# Processor.net
KiCad netlist of a schematic drawn in Altium Designer
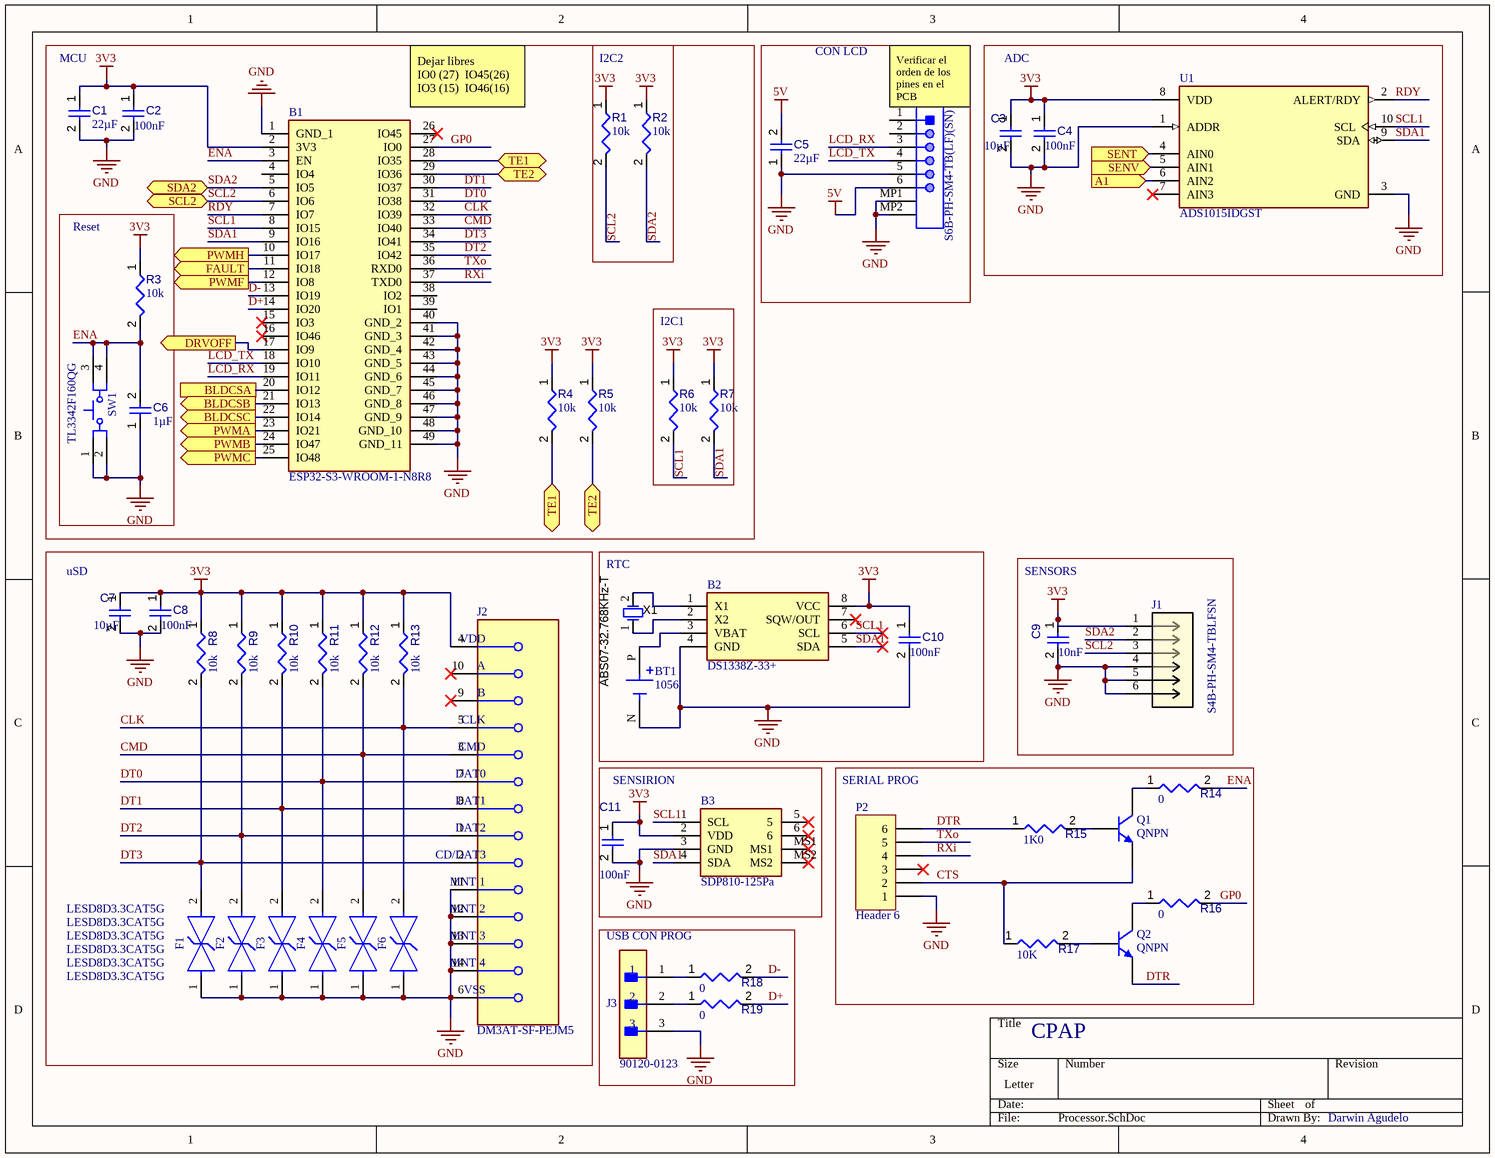
[diagram p0: Processor.SchDoc]

(export (version "E")
  (design (tool "Eeschema 10.0.6"))
  (components
    (comp (ref "B1")
      (value "ESP32-S3-WROOM-1-N8R8")
      (footprint "ESP32S3WROOM1N8R8")
      (fields (field (name "MOUSER PART NUMBER") "356-EP32S3WROOM1N8R8"))
      (libsource (lib "ESP32-S3-WROOM-1-N8R8") (part "ESP32-S3-WROOM-1-N8R8"))
    )
    (comp (ref "B2")
      (value "DS1338Z-33+")
      (footprint "SOIC127P600X175-8N")
      (fields (field (name "MOUSER PART NUMBER") "700-DS1338Z-33"))
      (libsource (lib "DS1338Z-33+") (part "DS1338Z-33+"))
    )
    (comp (ref "B3")
      (value "SDP810-125Pa")
      (footprint "SDP810125Pa")
      (description "Sensirion SDP810-125PA, Differential Pressure Sensor +125Pa 4-Pin")
      (fields
        (field (name "MOUSER PART NUMBER") "403-SDP810-125PA")
        (field (name "ARROW PART NUMBER") "SDP810-125PA")
      )
      (libsource (lib "SDP810-125Pa") (part "SDP810-125Pa"))
    )
    (comp (ref "BT1") (value "1056") (footprint "BAT_1056") (libsource (lib "1056") (part "1056")))
    (comp (ref "C1")
      (value "22µF")
      (footprint "CAPC0805(2012)145_L")
      (description "Chip Capacitor, 22µF +/-40%, 16V, 0805, Thickness 1.45 mm")
      (fields (field (name "TOLERANCE") "5%") (field (name "Comment") "Capacitor 22µF +/-40% 16V 0805"))
      (libsource (lib "UdeA") (part "CAP-NP-2"))
    )
    (comp (ref "C2")
      (value "100nF")
      (footprint "CAPC1608X90X40NL10T20")
      (description "Chip Capacitor, 100 nF, +/- 10%, 50 V, 0603 (1608 Metric)")
      (fields (field (name "TOLERANCE") "10%") (field (name "Comment") "Capacitor 100 nF +/-10% 50 V 0603"))
      (libsource (lib "UdeA") (part "CAP-NP-2"))
    )
    (comp (ref "C3")
      (value "10µF")
      (footprint "CAPC0805(2012)145_L")
      (description "Chip Capacitor, 22µF +/-40%, 16V, 0805, Thickness 1.45 mm")
      (fields (field (name "TOLERANCE") "5%") (field (name "Comment") "Capacitor 22µF +/-40% 16V 0805"))
      (libsource (lib "UdeA") (part "CAP-NP-2"))
    )
    (comp (ref "C4")
      (value "100nF")
      (footprint "CAPC1608X90X40NL10T20")
      (description "Chip Capacitor, 100 nF, +/- 10%, 50 V, 0603 (1608 Metric)")
      (fields (field (name "TOLERANCE") "10%") (field (name "Comment") "Capacitor 100 nF +/-10% 50 V 0603"))
      (libsource (lib "UdeA") (part "CAP-NP-2"))
    )
    (comp (ref "C5")
      (value "22µF")
      (footprint "CAPC0805(2012)145_L")
      (description "Chip Capacitor, 22µF +/-40%, 16V, 0805, Thickness 1.45 mm")
      (fields (field (name "TOLERANCE") "5%") (field (name "Comment") "Capacitor 22µF +/-40% 16V 0805"))
      (libsource (lib "UdeA") (part "CAP-NP-2"))
    )
    (comp (ref "C6")
      (value "1µF")
      (footprint "CAPC0603(1608)100_L")
      (description "Chip Capacitor, 1µF +/-40%, 50V, 0603, Thickness 1 mm")
      (fields (field (name "TOLERANCE") "10%") (field (name "Comment") "Capacitor 1µF +/-40% 50V 0603"))
      (libsource (lib "UdeA") (part "CAP-NP-2"))
    )
    (comp (ref "C7")
      (value "10µF")
      (footprint "CAPC0805(2012)145_L")
      (description "Chip Capacitor, 22µF +/-40%, 16V, 0805, Thickness 1.45 mm")
      (fields (field (name "TOLERANCE") "5%") (field (name "Comment") "Capacitor 22µF +/-40% 16V 0805"))
      (libsource (lib "UdeA") (part "CAP-NP-2"))
    )
    (comp (ref "C8")
      (value "100nF")
      (footprint "CAPC1608X90X40NL10T20")
      (description "Chip Capacitor, 100 nF, +/- 10%, 50 V, 0603 (1608 Metric)")
      (fields (field (name "TOLERANCE") "10%") (field (name "Comment") "Capacitor 100 nF +/-10% 50 V 0603"))
      (libsource (lib "UdeA") (part "CAP-NP-2"))
    )
    (comp (ref "C9")
      (value "10nF")
      (footprint "CAPC1608X90X40NL10T20")
      (description "Chip Capacitor, 100 nF, +/- 10%, 50 V, 0603 (1608 Metric)")
      (fields (field (name "TOLERANCE") "10%") (field (name "Comment") "Capacitor 100 nF +/-10% 50 V 0603"))
      (libsource (lib "UdeA") (part "CAP-NP-2"))
    )
    (comp (ref "C10")
      (value "100nF")
      (footprint "CAPC1608X90X40NL10T20")
      (description "Chip Capacitor, 100 nF, +/- 10%, 50 V, 0603 (1608 Metric)")
      (fields (field (name "TOLERANCE") "10%") (field (name "Comment") "Capacitor 100 nF +/-10% 50 V 0603"))
      (libsource (lib "UdeA") (part "CAP-NP-2"))
    )
    (comp (ref "C11")
      (value "100nF")
      (footprint "CAPC1608X90X40NL10T20")
      (description "Chip Capacitor, 100 nF, +/- 10%, 50 V, 0603 (1608 Metric)")
      (fields (field (name "TOLERANCE") "10%") (field (name "Comment") "Capacitor 100 nF +/-10% 50 V 0603"))
      (libsource (lib "UdeA") (part "CAP-NP-2"))
    )
    (comp (ref "F1")
      (value "LESD8D3.3CAT5G")
      (footprint "FP-ESDALC5-1BM2-MFG")
      (description "ESDALC5-1BM2 ESD Suppressors / TVS Diodes Single Line Transil Vbr 5V min 26pF 0")
      (libsource (lib "Altium Content Vault") (part "a9b0225688e8abec59830331bad87f8"))
    )
    (comp (ref "F2")
      (value "LESD8D3.3CAT5G")
      (footprint "FP-ESDALC5-1BM2-MFG")
      (description "ESDALC5-1BM2 ESD Suppressors / TVS Diodes Single Line Transil Vbr 5V min 26pF 0")
      (libsource (lib "Altium Content Vault") (part "a9b0225688e8abec59830331bad87f8"))
    )
    (comp (ref "F3")
      (value "LESD8D3.3CAT5G")
      (footprint "FP-ESDALC5-1BM2-MFG")
      (description "ESDALC5-1BM2 ESD Suppressors / TVS Diodes Single Line Transil Vbr 5V min 26pF 0")
      (libsource (lib "Altium Content Vault") (part "a9b0225688e8abec59830331bad87f8"))
    )
    (comp (ref "F4")
      (value "LESD8D3.3CAT5G")
      (footprint "FP-ESDALC5-1BM2-MFG")
      (description "ESDALC5-1BM2 ESD Suppressors / TVS Diodes Single Line Transil Vbr 5V min 26pF 0")
      (libsource (lib "Altium Content Vault") (part "a9b0225688e8abec59830331bad87f8"))
    )
    (comp (ref "F5")
      (value "LESD8D3.3CAT5G")
      (footprint "FP-ESDALC5-1BM2-MFG")
      (description "ESDALC5-1BM2 ESD Suppressors / TVS Diodes Single Line Transil Vbr 5V min 26pF 0")
      (libsource (lib "Altium Content Vault") (part "a9b0225688e8abec59830331bad87f8"))
    )
    (comp (ref "F6")
      (value "LESD8D3.3CAT5G")
      (footprint "FP-ESDALC5-1BM2-MFG")
      (description "ESDALC5-1BM2 ESD Suppressors / TVS Diodes Single Line Transil Vbr 5V min 26pF 0")
      (libsource (lib "Altium Content Vault") (part "a9b0225688e8abec59830331bad87f8"))
    )
    (comp (ref "J1")
      (value "S4B-PH-SM4-TBLFSN")
      (footprint "CONN_S4B-PH-SM4-TBLFSN_JST")
      (description "No Description Available")
      (libsource (lib "S4B-PH-SM4-TBLFSN") (part "S4B-PH-SM4-TBLFSN"))
    )
    (comp (ref "J2")
      (value "DM3AT-SF-PEJM5")
      (footprint "FP-DM3AT-SF-PEJM5-MFG")
      (description "CONN MICRO SD CARD PUSH-PUSH R/A")
      (libsource (lib "Altium Content Vault") (part "a4e64ec0820c4377148bc1329e4c440"))
    )
    (comp (ref "J3")
      (value "90120-0123")
      (footprint "FP-90120-0123-MFG")
      (description "CONN HEADER VERT 3POS 2.54MM")
      (libsource (lib "Altium Content Vault") (part "0d3f023dd272f625e17a2be33dea85f"))
    )
    (comp (ref "P1")
      (value "S6B-PH-SM4-TB(LF)(SN)")
      (footprint "JST-S6B-PH-SM4-TB(LF)(SN)_V")
      (description "Male Header, Pitch 2 mm, 1 x 6 Position, Height 5.5 mm, -25 to 85 degC")
      (fields (field (name "MANUFACTURER") "JST"))
      (libsource (lib "Altium Content Vault") (part "CN-1P-2M-R6"))
    )
    (comp (ref "P2")
      (value "Header 6")
      (footprint "HDR1X6")
      (description "Header, 6-Pin")
      (fields (field (name "PUBLISHER") "Altium Limited"))
      (libsource (lib "Miscellaneous Connectors") (part "Header 6"))
    )
    (comp (ref "Q1")
      (value "QNPN")
      (footprint "SOT-23B_L")
      (description "NPN Bipolar Transistor")
      (fields (field (name "PUBLISHER") "Altium Limited"))
      (libsource (lib "Miscellaneous Devices") (part "QNPN"))
    )
    (comp (ref "Q2")
      (value "QNPN")
      (footprint "SOT-23B_L")
      (description "NPN Bipolar Transistor")
      (fields (field (name "PUBLISHER") "Altium Limited"))
      (libsource (lib "Miscellaneous Devices") (part "QNPN"))
    )
    (comp (ref "R1")
      (value "10k")
      (footprint "RESC1608X55X25ML10T15")
      (description "Chip Resistor, 10 KOhm, +/- 1%, 01 W, -55 to 155 degC, 0603 (1608 Metric)")
      (fields (field (name "POWER") "100mW") (field (name "TOLERANCE") "1%"))
      (libsource (lib "UdeA") (part "RES-2"))
    )
    (comp (ref "R2")
      (value "10k")
      (footprint "RESC1608X55X25ML10T15")
      (description "Chip Resistor, 10 KOhm, +/- 1%, 01 W, -55 to 155 degC, 0603 (1608 Metric)")
      (fields (field (name "POWER") "100mW") (field (name "TOLERANCE") "1%"))
      (libsource (lib "UdeA") (part "RES-2"))
    )
    (comp (ref "R3")
      (value "10k")
      (footprint "RESC1608X55X25ML10T15")
      (description "Chip Resistor, 10 KOhm, +/- 1%, 01 W, -55 to 155 degC, 0603 (1608 Metric)")
      (fields (field (name "POWER") "100mW") (field (name "TOLERANCE") "1%"))
      (libsource (lib "UdeA") (part "RES-2"))
    )
    (comp (ref "R4")
      (value "10k")
      (footprint "RESC1608X55X25ML10T15")
      (description "Chip Resistor, 10 KOhm, +/- 1%, 01 W, -55 to 155 degC, 0603 (1608 Metric)")
      (fields (field (name "POWER") "100mW") (field (name "TOLERANCE") "1%"))
      (libsource (lib "UdeA") (part "RES-2"))
    )
    (comp (ref "R5")
      (value "10k")
      (footprint "RESC1608X55X25ML10T15")
      (description "Chip Resistor, 10 KOhm, +/- 1%, 01 W, -55 to 155 degC, 0603 (1608 Metric)")
      (fields (field (name "POWER") "100mW") (field (name "TOLERANCE") "1%"))
      (libsource (lib "UdeA") (part "RES-2"))
    )
    (comp (ref "R6")
      (value "10k")
      (footprint "RESC1608X55X25ML10T15")
      (description "Chip Resistor, 10 KOhm, +/- 1%, 01 W, -55 to 155 degC, 0603 (1608 Metric)")
      (fields (field (name "POWER") "100mW") (field (name "TOLERANCE") "1%"))
      (libsource (lib "UdeA") (part "RES-2"))
    )
    (comp (ref "R7")
      (value "10k")
      (footprint "RESC1608X55X25ML10T15")
      (description "Chip Resistor, 10 KOhm, +/- 1%, 01 W, -55 to 155 degC, 0603 (1608 Metric)")
      (fields (field (name "POWER") "100mW") (field (name "TOLERANCE") "1%"))
      (libsource (lib "UdeA") (part "RES-2"))
    )
    (comp (ref "R8")
      (value "10k")
      (footprint "RESC1608X55X25ML10T15")
      (description "Chip Resistor, 10 KOhm, +/- 1%, 01 W, -55 to 155 degC, 0603 (1608 Metric)")
      (fields (field (name "POWER") "100mW") (field (name "TOLERANCE") "1%"))
      (libsource (lib "UdeA") (part "RES-2"))
    )
    (comp (ref "R9")
      (value "10k")
      (footprint "RESC1608X55X25ML10T15")
      (description "Chip Resistor, 10 KOhm, +/- 1%, 01 W, -55 to 155 degC, 0603 (1608 Metric)")
      (fields (field (name "POWER") "100mW") (field (name "TOLERANCE") "1%"))
      (libsource (lib "UdeA") (part "RES-2"))
    )
    (comp (ref "R10")
      (value "10k")
      (footprint "RESC1608X55X25ML10T15")
      (description "Chip Resistor, 10 KOhm, +/- 1%, 01 W, -55 to 155 degC, 0603 (1608 Metric)")
      (fields (field (name "POWER") "100mW") (field (name "TOLERANCE") "1%"))
      (libsource (lib "UdeA") (part "RES-2"))
    )
    (comp (ref "R11")
      (value "10k")
      (footprint "RESC1608X55X25ML10T15")
      (description "Chip Resistor, 10 KOhm, +/- 1%, 01 W, -55 to 155 degC, 0603 (1608 Metric)")
      (fields (field (name "POWER") "100mW") (field (name "TOLERANCE") "1%"))
      (libsource (lib "UdeA") (part "RES-2"))
    )
    (comp (ref "R12")
      (value "10k")
      (footprint "RESC1608X55X25ML10T15")
      (description "Chip Resistor, 10 KOhm, +/- 1%, 01 W, -55 to 155 degC, 0603 (1608 Metric)")
      (fields (field (name "POWER") "100mW") (field (name "TOLERANCE") "1%"))
      (libsource (lib "UdeA") (part "RES-2"))
    )
    (comp (ref "R13")
      (value "10k")
      (footprint "RESC1608X55X25ML10T15")
      (description "Chip Resistor, 10 KOhm, +/- 1%, 01 W, -55 to 155 degC, 0603 (1608 Metric)")
      (fields (field (name "POWER") "100mW") (field (name "TOLERANCE") "1%"))
      (libsource (lib "UdeA") (part "RES-2"))
    )
    (comp (ref "R14")
      (value "0")
      (footprint "RESC1608X55X25ML10T15")
      (description "Chip Resistor, 10 KOhm, +/- 1%, 01 W, -55 to 155 degC, 0603 (1608 Metric)")
      (fields (field (name "POWER") "100mW") (field (name "TOLERANCE") "1%"))
      (libsource (lib "UdeA") (part "RES-2"))
    )
    (comp (ref "R15")
      (value "1K0")
      (footprint "RESC1608X55X25ML10T15")
      (description "Chip Resistor, 10 KOhm, +/- 1%, 01 W, -55 to 155 degC, 0603 (1608 Metric)")
      (fields (field (name "POWER") "100mW") (field (name "TOLERANCE") "1%"))
      (libsource (lib "UdeA") (part "RES-2"))
    )
    (comp (ref "R16")
      (value "0")
      (footprint "RESC1608X55X25ML10T15")
      (description "Chip Resistor, 10 KOhm, +/- 1%, 01 W, -55 to 155 degC, 0603 (1608 Metric)")
      (fields (field (name "POWER") "100mW") (field (name "TOLERANCE") "1%"))
      (libsource (lib "UdeA") (part "RES-2"))
    )
    (comp (ref "R17")
      (value "10K")
      (footprint "RESC1608X55X25ML10T15")
      (description "Chip Resistor, 10 KOhm, +/- 1%, 01 W, -55 to 155 degC, 0603 (1608 Metric)")
      (fields (field (name "POWER") "100mW") (field (name "TOLERANCE") "1%"))
      (libsource (lib "UdeA") (part "RES-2"))
    )
    (comp (ref "R18")
      (value "0")
      (footprint "RESC1608X55X25ML10T15")
      (description "Chip Resistor, 10 KOhm, +/- 1%, 01 W, -55 to 155 degC, 0603 (1608 Metric)")
      (fields (field (name "POWER") "100mW") (field (name "TOLERANCE") "1%"))
      (libsource (lib "UdeA") (part "RES-2"))
    )
    (comp (ref "R19")
      (value "0")
      (footprint "RESC1608X55X25ML10T15")
      (description "Chip Resistor, 10 KOhm, +/- 1%, 01 W, -55 to 155 degC, 0603 (1608 Metric)")
      (fields (field (name "POWER") "100mW") (field (name "TOLERANCE") "1%"))
      (libsource (lib "altium-import") (part "root_0_RES-2_"))
    )
    (comp (ref "SW1")
      (value "TL3342F160QG")
      (footprint "ESWI-TL3342F160QG_V")
      (description "Tactile Switch, SPST-NO, 50 mA, 12 V, 4-Pin SMD, RoHS, Tape and Reel")
      (fields (field (name "MANUFACTURER") "E-Switch"))
      (libsource (lib "UdeA") (part "SW-SPST-NO-4"))
    )
    (comp (ref "U1")
      (value "ADS1015IDGST")
      (footprint "FP-DGS0010A-MFG")
      (description "IC ADC 12BIT SIGMA-DELTA 10VSSOP")
      (libsource (lib "Altium Content Vault") (part "0fb225032f4bd54fd540a872e776a50"))
    )
    (comp (ref "X1")
      (value "ABS07-32.768KHz-T")
      (footprint "ABRA-ABS07-2_V")
      (fields (field (name "TOLERANCE") "20ppm") (field (name "MANUFACTURER") "Abracon"))
      (libsource (lib "UdeA") (part "ABRA-ABS07-2"))
    )
  )
  (nets
    (net (code "1") (name "/A1") (class "Default")
      (node (ref "U1") (pin "6") (pinfunction "AIN2_6") (pintype "passive"))
    )
    (net (code "2") (name "/BLDCSA") (class "Default")
      (node (ref "B1") (pin "20") (pinfunction "IO12_20") (pintype "passive"))
    )
    (net (code "3") (name "/BLDCSB") (class "Default")
      (node (ref "B1") (pin "21") (pinfunction "IO13_21") (pintype "passive"))
    )
    (net (code "4") (name "/BLDCSC") (class "Default")
      (node (ref "B1") (pin "22") (pinfunction "IO14_22") (pintype "passive"))
    )
    (net (code "5") (name "/CLK") (class "Default")
      (node (ref "B1") (pin "32") (pinfunction "IO39_32") (pintype "passive"))
      (node (ref "F6") (pin "2") (pinfunction "I/O2_2") (pintype "passive"))
      (node (ref "J2") (pin "5") (pinfunction "CLK_5") (pintype "passive"))
      (node (ref "R13") (pin "2") (pinfunction "2_2") (pintype "passive"))
    )
    (net (code "6") (name "/CMD") (class "Default")
      (node (ref "B1") (pin "33") (pinfunction "IO40_33") (pintype "passive"))
      (node (ref "F5") (pin "2") (pinfunction "I/O2_2") (pintype "passive"))
      (node (ref "J2") (pin "3") (pinfunction "CMD_3") (pintype "passive"))
      (node (ref "R12") (pin "2") (pinfunction "2_2") (pintype "passive"))
    )
    (net (code "7") (name "/CTS") (class "Default")
      (node (ref "P2") (pin "2") (pinfunction "2_2") (pintype "passive"))
      (node (ref "Q1") (pin "3") (pinfunction "E_3") (pintype "passive"))
      (node (ref "R17") (pin "1") (pinfunction "1_1") (pintype "passive"))
    )
    (net (code "8") (name "/D+") (class "Default")
      (node (ref "B1") (pin "14") (pinfunction "IO20_14") (pintype "passive"))
      (node (ref "R19") (pin "2") (pinfunction "2_2") (pintype "passive"))
    )
    (net (code "9") (name "/D-") (class "Default")
      (node (ref "B1") (pin "13") (pinfunction "IO19_13") (pintype "passive"))
      (node (ref "R18") (pin "2") (pinfunction "2_2") (pintype "passive"))
    )
    (net (code "10") (name "/DRVOFF") (class "Default")
      (node (ref "B1") (pin "17") (pinfunction "IO9_17") (pintype "passive"))
    )
    (net (code "11") (name "/DT0") (class "Default")
      (node (ref "B1") (pin "31") (pinfunction "IO38_31") (pintype "passive"))
      (node (ref "F4") (pin "2") (pinfunction "I/O2_2") (pintype "passive"))
      (node (ref "J2") (pin "7") (pinfunction "DAT0_7") (pintype "passive"))
      (node (ref "R11") (pin "2") (pinfunction "2_2") (pintype "passive"))
    )
    (net (code "12") (name "/DT1") (class "Default")
      (node (ref "B1") (pin "30") (pinfunction "IO37_30") (pintype "passive"))
      (node (ref "F3") (pin "2") (pinfunction "I/O2_2") (pintype "passive"))
      (node (ref "J2") (pin "8") (pinfunction "DAT1_8") (pintype "passive"))
      (node (ref "R10") (pin "2") (pinfunction "2_2") (pintype "passive"))
    )
    (net (code "13") (name "/DT2") (class "Default")
      (node (ref "B1") (pin "35") (pinfunction "IO42_35") (pintype "passive"))
      (node (ref "F2") (pin "2") (pinfunction "I/O2_2") (pintype "passive"))
      (node (ref "J2") (pin "1") (pinfunction "DAT2_1") (pintype "passive"))
      (node (ref "R9") (pin "2") (pinfunction "2_2") (pintype "passive"))
    )
    (net (code "14") (name "/DT3") (class "Default")
      (node (ref "B1") (pin "34") (pinfunction "IO41_34") (pintype "passive"))
      (node (ref "F1") (pin "2") (pinfunction "I/O2_2") (pintype "passive"))
      (node (ref "J2") (pin "2") (pinfunction "CD/DAT3_2") (pintype "passive"))
      (node (ref "R8") (pin "2") (pinfunction "2_2") (pintype "passive"))
    )
    (net (code "15") (name "/DTR") (class "Default")
      (node (ref "P2") (pin "6") (pinfunction "6_6") (pintype "passive"))
      (node (ref "Q2") (pin "3") (pinfunction "E_3") (pintype "passive"))
      (node (ref "R15") (pin "1") (pinfunction "1_1") (pintype "passive"))
    )
    (net (code "16") (name "/ENA") (class "Default")
      (node (ref "B1") (pin "3") (pinfunction "EN_3") (pintype "passive"))
      (node (ref "C6") (pin "2") (pinfunction "2_2") (pintype "passive"))
      (node (ref "R14") (pin "2") (pinfunction "2_2") (pintype "passive"))
      (node (ref "R3") (pin "2") (pinfunction "2_2") (pintype "passive"))
      (node (ref "SW1") (pin "3") (pinfunction "3_3") (pintype "passive"))
      (node (ref "SW1") (pin "4") (pinfunction "4_4") (pintype "passive"))
    )
    (net (code "17") (name "/FAULT") (class "Default")
      (node (ref "B1") (pin "11") (pinfunction "IO18_11") (pintype "passive"))
    )
    (net (code "18") (name "/GP0") (class "Default")
      (node (ref "B1") (pin "27") (pinfunction "IO0_27") (pintype "passive"))
      (node (ref "R16") (pin "2") (pinfunction "2_2") (pintype "passive"))
    )
    (net (code "19") (name "/LCD_RX") (class "Default")
      (node (ref "B1") (pin "19") (pinfunction "IO11_19") (pintype "passive"))
      (node (ref "P1") (pin "3") (pinfunction "3_3") (pintype "passive"))
    )
    (net (code "20") (name "/LCD_TX") (class "Default")
      (node (ref "B1") (pin "18") (pinfunction "IO10_18") (pintype "passive"))
      (node (ref "P1") (pin "4") (pinfunction "4_4") (pintype "passive"))
    )
    (net (code "21") (name "/PWMA") (class "Default")
      (node (ref "B1") (pin "23") (pinfunction "IO21_23") (pintype "passive"))
    )
    (net (code "22") (name "/PWMB") (class "Default")
      (node (ref "B1") (pin "24") (pinfunction "IO47_24") (pintype "passive"))
    )
    (net (code "23") (name "/PWMC") (class "Default")
      (node (ref "B1") (pin "25") (pinfunction "IO48_25") (pintype "passive"))
    )
    (net (code "24") (name "/PWMF") (class "Default")
      (node (ref "B1") (pin "12") (pinfunction "IO8_12") (pintype "passive"))
    )
    (net (code "25") (name "/PWMH") (class "Default")
      (node (ref "B1") (pin "10") (pinfunction "IO17_10") (pintype "passive"))
    )
    (net (code "26") (name "/RDY") (class "Default")
      (node (ref "B1") (pin "7") (pinfunction "IO7_7") (pintype "passive"))
      (node (ref "U1") (pin "2") (pinfunction "ALERT/RDY_2") (pintype "output"))
    )
    (net (code "27") (name "/RXi") (class "Default")
      (node (ref "B1") (pin "37") (pinfunction "TXD0_37") (pintype "passive"))
      (node (ref "P2") (pin "4") (pinfunction "4_4") (pintype "passive"))
    )
    (net (code "28") (name "/SCL1") (class "Default")
      (node (ref "B1") (pin "8") (pinfunction "IO15_8") (pintype "passive"))
      (node (ref "B2") (pin "6") (pinfunction "SCL_6") (pintype "passive"))
      (node (ref "B3") (pin "1") (pinfunction "SCL_1") (pintype "passive"))
      (node (ref "R6") (pin "2") (pinfunction "2_2") (pintype "passive"))
      (node (ref "U1") (pin "10") (pinfunction "SCL_10") (pintype "input"))
    )
    (net (code "29") (name "/SCL2") (class "Default")
      (node (ref "B1") (pin "6") (pinfunction "IO6_6") (pintype "passive"))
      (node (ref "J1") (pin "3") (pinfunction "3_3") (pintype "passive"))
      (node (ref "R1") (pin "2") (pinfunction "2_2") (pintype "passive"))
    )
    (net (code "30") (name "/SDA1") (class "Default")
      (node (ref "B1") (pin "9") (pinfunction "IO16_9") (pintype "passive"))
      (node (ref "B2") (pin "5") (pinfunction "SDA_5") (pintype "passive"))
      (node (ref "B3") (pin "4") (pinfunction "SDA_4") (pintype "passive"))
      (node (ref "R7") (pin "2") (pinfunction "2_2") (pintype "passive"))
      (node (ref "U1") (pin "9") (pinfunction "SDA_9") (pintype "bidirectional"))
    )
    (net (code "31") (name "/SDA2") (class "Default")
      (node (ref "B1") (pin "5") (pinfunction "IO5_5") (pintype "passive"))
      (node (ref "J1") (pin "2") (pinfunction "2_2") (pintype "passive"))
      (node (ref "R2") (pin "2") (pinfunction "2_2") (pintype "passive"))
    )
    (net (code "32") (name "/SENT") (class "Default")
      (node (ref "U1") (pin "4") (pinfunction "AIN0_4") (pintype "passive"))
    )
    (net (code "33") (name "/SENV") (class "Default")
      (node (ref "U1") (pin "5") (pinfunction "AIN1_5") (pintype "passive"))
    )
    (net (code "34") (name "/TE1") (class "Default")
      (node (ref "B1") (pin "28") (pinfunction "IO35_28") (pintype "passive"))
      (node (ref "R4") (pin "2") (pinfunction "2_2") (pintype "passive"))
    )
    (net (code "35") (name "/TE2") (class "Default")
      (node (ref "B1") (pin "29") (pinfunction "IO36_29") (pintype "passive"))
      (node (ref "R5") (pin "2") (pinfunction "2_2") (pintype "passive"))
    )
    (net (code "36") (name "/TXo") (class "Default")
      (node (ref "B1") (pin "36") (pinfunction "RXD0_36") (pintype "passive"))
      (node (ref "P2") (pin "5") (pinfunction "5_5") (pintype "passive"))
    )
    (net (code "37") (name "3V3") (class "Default")
      (node (ref "B1") (pin "2") (pinfunction "3V3_2") (pintype "power_in"))
      (node (ref "B2") (pin "8") (pinfunction "VCC_8") (pintype "passive"))
      (node (ref "B3") (pin "2") (pinfunction "VDD_2") (pintype "passive"))
      (node (ref "C1") (pin "1") (pinfunction "1_1") (pintype "passive"))
      (node (ref "C10") (pin "1") (pinfunction "1_1") (pintype "passive"))
      (node (ref "C11") (pin "1") (pinfunction "1_1") (pintype "passive"))
      (node (ref "C2") (pin "1") (pinfunction "1_1") (pintype "passive"))
      (node (ref "C3") (pin "1") (pinfunction "1_1") (pintype "passive"))
      (node (ref "C4") (pin "1") (pinfunction "1_1") (pintype "passive"))
      (node (ref "C7") (pin "1") (pinfunction "1_1") (pintype "passive"))
      (node (ref "C8") (pin "1") (pinfunction "1_1") (pintype "passive"))
      (node (ref "C9") (pin "1") (pinfunction "1_1") (pintype "passive"))
      (node (ref "J1") (pin "1") (pinfunction "1_1") (pintype "passive"))
      (node (ref "J2") (pin "4") (pinfunction "VDD_4") (pintype "power_in"))
      (node (ref "R1") (pin "1") (pinfunction "1_1") (pintype "passive"))
      (node (ref "R10") (pin "1") (pinfunction "1_1") (pintype "passive"))
      (node (ref "R11") (pin "1") (pinfunction "1_1") (pintype "passive"))
      (node (ref "R12") (pin "1") (pinfunction "1_1") (pintype "passive"))
      (node (ref "R13") (pin "1") (pinfunction "1_1") (pintype "passive"))
      (node (ref "R2") (pin "1") (pinfunction "1_1") (pintype "passive"))
      (node (ref "R3") (pin "1") (pinfunction "1_1") (pintype "passive"))
      (node (ref "R4") (pin "1") (pinfunction "1_1") (pintype "passive"))
      (node (ref "R5") (pin "1") (pinfunction "1_1") (pintype "passive"))
      (node (ref "R6") (pin "1") (pinfunction "1_1") (pintype "passive"))
      (node (ref "R7") (pin "1") (pinfunction "1_1") (pintype "passive"))
      (node (ref "R8") (pin "1") (pinfunction "1_1") (pintype "passive"))
      (node (ref "R9") (pin "1") (pinfunction "1_1") (pintype "passive"))
      (node (ref "U1") (pin "8") (pinfunction "VDD_8") (pintype "power_in"))
    )
    (net (code "38") (name "5V") (class "Default")
      (node (ref "C5") (pin "2") (pinfunction "2_2") (pintype "passive"))
      (node (ref "P1") (pin "6") (pinfunction "6_6") (pintype "passive"))
    )
    (net (code "39") (name "GND") (class "Default")
      (node (ref "B1") (pin "1") (pinfunction "GND_1_1") (pintype "passive"))
      (node (ref "B1") (pin "40") (pinfunction "GND_2_40") (pintype "passive"))
      (node (ref "B1") (pin "41") (pinfunction "GND_3_41") (pintype "passive"))
      (node (ref "B1") (pin "42") (pinfunction "GND_4_42") (pintype "passive"))
      (node (ref "B1") (pin "43") (pinfunction "GND_5_43") (pintype "passive"))
      (node (ref "B1") (pin "44") (pinfunction "GND_6_44") (pintype "passive"))
      (node (ref "B1") (pin "45") (pinfunction "GND_7_45") (pintype "passive"))
      (node (ref "B1") (pin "46") (pinfunction "GND_8_46") (pintype "passive"))
      (node (ref "B1") (pin "47") (pinfunction "GND_9_47") (pintype "passive"))
      (node (ref "B1") (pin "48") (pinfunction "GND_10_48") (pintype "passive"))
      (node (ref "B1") (pin "49") (pinfunction "GND_11_49") (pintype "passive"))
      (node (ref "B2") (pin "4") (pinfunction "GND_4") (pintype "passive"))
      (node (ref "B3") (pin "3") (pinfunction "GND_3") (pintype "passive"))
      (node (ref "BT1") (pin "N") (pinfunction "NEG_N") (pintype "passive"))
      (node (ref "C1") (pin "2") (pinfunction "2_2") (pintype "passive"))
      (node (ref "C10") (pin "2") (pinfunction "2_2") (pintype "passive"))
      (node (ref "C11") (pin "2") (pinfunction "2_2") (pintype "passive"))
      (node (ref "C2") (pin "2") (pinfunction "2_2") (pintype "passive"))
      (node (ref "C3") (pin "2") (pinfunction "2_2") (pintype "passive"))
      (node (ref "C4") (pin "2") (pinfunction "2_2") (pintype "passive"))
      (node (ref "C5") (pin "1") (pinfunction "1_1") (pintype "passive"))
      (node (ref "C6") (pin "1") (pinfunction "1_1") (pintype "passive"))
      (node (ref "C7") (pin "2") (pinfunction "2_2") (pintype "passive"))
      (node (ref "C8") (pin "2") (pinfunction "2_2") (pintype "passive"))
      (node (ref "C9") (pin "2") (pinfunction "2_2") (pintype "passive"))
      (node (ref "F1") (pin "1") (pinfunction "I/O1_1") (pintype "passive"))
      (node (ref "F2") (pin "1") (pinfunction "I/O1_1") (pintype "passive"))
      (node (ref "F3") (pin "1") (pinfunction "I/O1_1") (pintype "passive"))
      (node (ref "F4") (pin "1") (pinfunction "I/O1_1") (pintype "passive"))
      (node (ref "F5") (pin "1") (pinfunction "I/O1_1") (pintype "passive"))
      (node (ref "F6") (pin "1") (pinfunction "I/O1_1") (pintype "passive"))
      (node (ref "J1") (pin "4") (pinfunction "4_4") (pintype "passive"))
      (node (ref "J1") (pin "5") (pinfunction "5_5") (pintype "passive"))
      (node (ref "J1") (pin "6") (pinfunction "6_6") (pintype "passive"))
      (node (ref "J2") (pin "11") (pinfunction "MNT_1_11") (pintype "passive"))
      (node (ref "J2") (pin "12") (pinfunction "MNT_2_12") (pintype "passive"))
      (node (ref "J2") (pin "13") (pinfunction "MNT_3_13") (pintype "passive"))
      (node (ref "J2") (pin "14") (pinfunction "MNT_4_14") (pintype "passive"))
      (node (ref "J2") (pin "6") (pinfunction "VSS_6") (pintype "power_in"))
      (node (ref "J3") (pin "3") (pinfunction "3_3") (pintype "passive"))
      (node (ref "P1") (pin "5") (pinfunction "5_5") (pintype "passive"))
      (node (ref "P1") (pin "MP1") (pinfunction "MP1_MP1") (pintype "passive"))
      (node (ref "P1") (pin "MP2") (pinfunction "MP2_MP2") (pintype "passive"))
      (node (ref "P2") (pin "1") (pinfunction "1_1") (pintype "passive"))
      (node (ref "SW1") (pin "1") (pinfunction "1_1") (pintype "passive"))
      (node (ref "SW1") (pin "2") (pinfunction "2_2") (pintype "passive"))
      (node (ref "U1") (pin "1") (pinfunction "ADDR_1") (pintype "input"))
      (node (ref "U1") (pin "3") (pinfunction "GND_3") (pintype "power_in"))
    )
    (net (code "40") (name "Net-(B2-VBAT)") (class "Default")
      (node (ref "B2") (pin "3") (pinfunction "VBAT_3") (pintype "passive"))
      (node (ref "BT1") (pin "P") (pinfunction "POS_P") (pintype "passive"))
    )
    (net (code "41") (name "Net-(B2-X1)") (class "Default")
      (node (ref "B2") (pin "1") (pinfunction "X1_1") (pintype "passive"))
      (node (ref "X1") (pin "2") (pinfunction "OSC2_2") (pintype "passive"))
    )
    (net (code "42") (name "Net-(B2-X2)") (class "Default")
      (node (ref "B2") (pin "2") (pinfunction "X2_2") (pintype "passive"))
      (node (ref "X1") (pin "1") (pinfunction "OSC1_1") (pintype "passive"))
    )
    (net (code "43") (name "Net-(J3-Pad1)") (class "Default")
      (node (ref "J3") (pin "1") (pinfunction "1_1") (pintype "passive"))
      (node (ref "R18") (pin "1") (pinfunction "1_1") (pintype "passive"))
    )
    (net (code "44") (name "Net-(J3-Pad2)") (class "Default")
      (node (ref "J3") (pin "2") (pinfunction "2_2") (pintype "passive"))
      (node (ref "R19") (pin "1") (pinfunction "1_1") (pintype "passive"))
    )
    (net (code "45") (name "Net-(Q1-B)") (class "Default")
      (node (ref "Q1") (pin "2") (pinfunction "B_2") (pintype "passive"))
      (node (ref "R15") (pin "2") (pinfunction "2_2") (pintype "passive"))
    )
    (net (code "46") (name "Net-(Q1-C)") (class "Default")
      (node (ref "Q1") (pin "1") (pinfunction "C_1") (pintype "passive"))
      (node (ref "R14") (pin "1") (pinfunction "1_1") (pintype "passive"))
    )
    (net (code "47") (name "Net-(Q2-B)") (class "Default")
      (node (ref "Q2") (pin "2") (pinfunction "B_2") (pintype "passive"))
      (node (ref "R17") (pin "2") (pinfunction "2_2") (pintype "passive"))
    )
    (net (code "48") (name "Net-(Q2-C)") (class "Default")
      (node (ref "Q2") (pin "1") (pinfunction "C_1") (pintype "passive"))
      (node (ref "R16") (pin "1") (pinfunction "1_1") (pintype "passive"))
    )
    (net (code "49") (name "unconnected-(B1-IO1-Pad39)") (class "Default")
      (node (ref "B1") (pin "39") (pinfunction "IO1_39") (pintype "passive"))
    )
    (net (code "50") (name "unconnected-(B1-IO2-Pad38)") (class "Default")
      (node (ref "B1") (pin "38") (pinfunction "IO2_38") (pintype "passive"))
    )
    (net (code "51") (name "unconnected-(B1-IO3-Pad15)") (class "Default")
      (node (ref "B1") (pin "15") (pinfunction "IO3_15") (pintype "passive+no_connect"))
    )
    (net (code "52") (name "unconnected-(B1-IO4-Pad4)") (class "Default")
      (node (ref "B1") (pin "4") (pinfunction "IO4_4") (pintype "passive"))
    )
    (net (code "53") (name "unconnected-(B1-IO45-Pad26)") (class "Default")
      (node (ref "B1") (pin "26") (pinfunction "IO45_26") (pintype "passive+no_connect"))
    )
    (net (code "54") (name "unconnected-(B1-IO46-Pad16)") (class "Default")
      (node (ref "B1") (pin "16") (pinfunction "IO46_16") (pintype "passive+no_connect"))
    )
    (net (code "55") (name "unconnected-(B2-SQW{slash}OUT-Pad7)") (class "Default")
      (node (ref "B2") (pin "7") (pinfunction "SQW/OUT_7") (pintype "passive+no_connect"))
    )
    (net (code "56") (name "unconnected-(B3-Pad5)") (class "Default")
      (node (ref "B3") (pin "5") (pinfunction "5_5") (pintype "passive+no_connect"))
    )
    (net (code "57") (name "unconnected-(B3-Pad6)") (class "Default")
      (node (ref "B3") (pin "6") (pinfunction "6_6") (pintype "passive+no_connect"))
    )
    (net (code "58") (name "unconnected-(B3-PadMS1)") (class "Default")
      (node (ref "B3") (pin "MS1") (pinfunction "MS1_MS1") (pintype "passive+no_connect"))
    )
    (net (code "59") (name "unconnected-(B3-PadMS2)") (class "Default")
      (node (ref "B3") (pin "MS2") (pinfunction "MS2_MS2") (pintype "passive+no_connect"))
    )
    (net (code "60") (name "unconnected-(J2-A-Pad10)") (class "Default")
      (node (ref "J2") (pin "10") (pinfunction "A_10") (pintype "passive+no_connect"))
    )
    (net (code "61") (name "unconnected-(J2-B-Pad9)") (class "Default")
      (node (ref "J2") (pin "9") (pinfunction "B_9") (pintype "passive+no_connect"))
    )
    (net (code "62") (name "unconnected-(P1-Pad1)") (class "Default")
      (node (ref "P1") (pin "1") (pinfunction "1_1") (pintype "passive"))
    )
    (net (code "63") (name "unconnected-(P1-Pad2)") (class "Default")
      (node (ref "P1") (pin "2") (pinfunction "2_2") (pintype "passive"))
    )
    (net (code "64") (name "unconnected-(P2-Pad3)") (class "Default")
      (node (ref "P2") (pin "3") (pinfunction "3_3") (pintype "passive+no_connect"))
    )
    (net (code "65") (name "unconnected-(U1-AIN3-Pad7)") (class "Default")
      (node (ref "U1") (pin "7") (pinfunction "AIN3_7") (pintype "passive+no_connect"))
    )
  )
)
